# MF_badge_2021_protoshield_ver_B.net
KiCad netlist of a schematic drawn in EAGLE
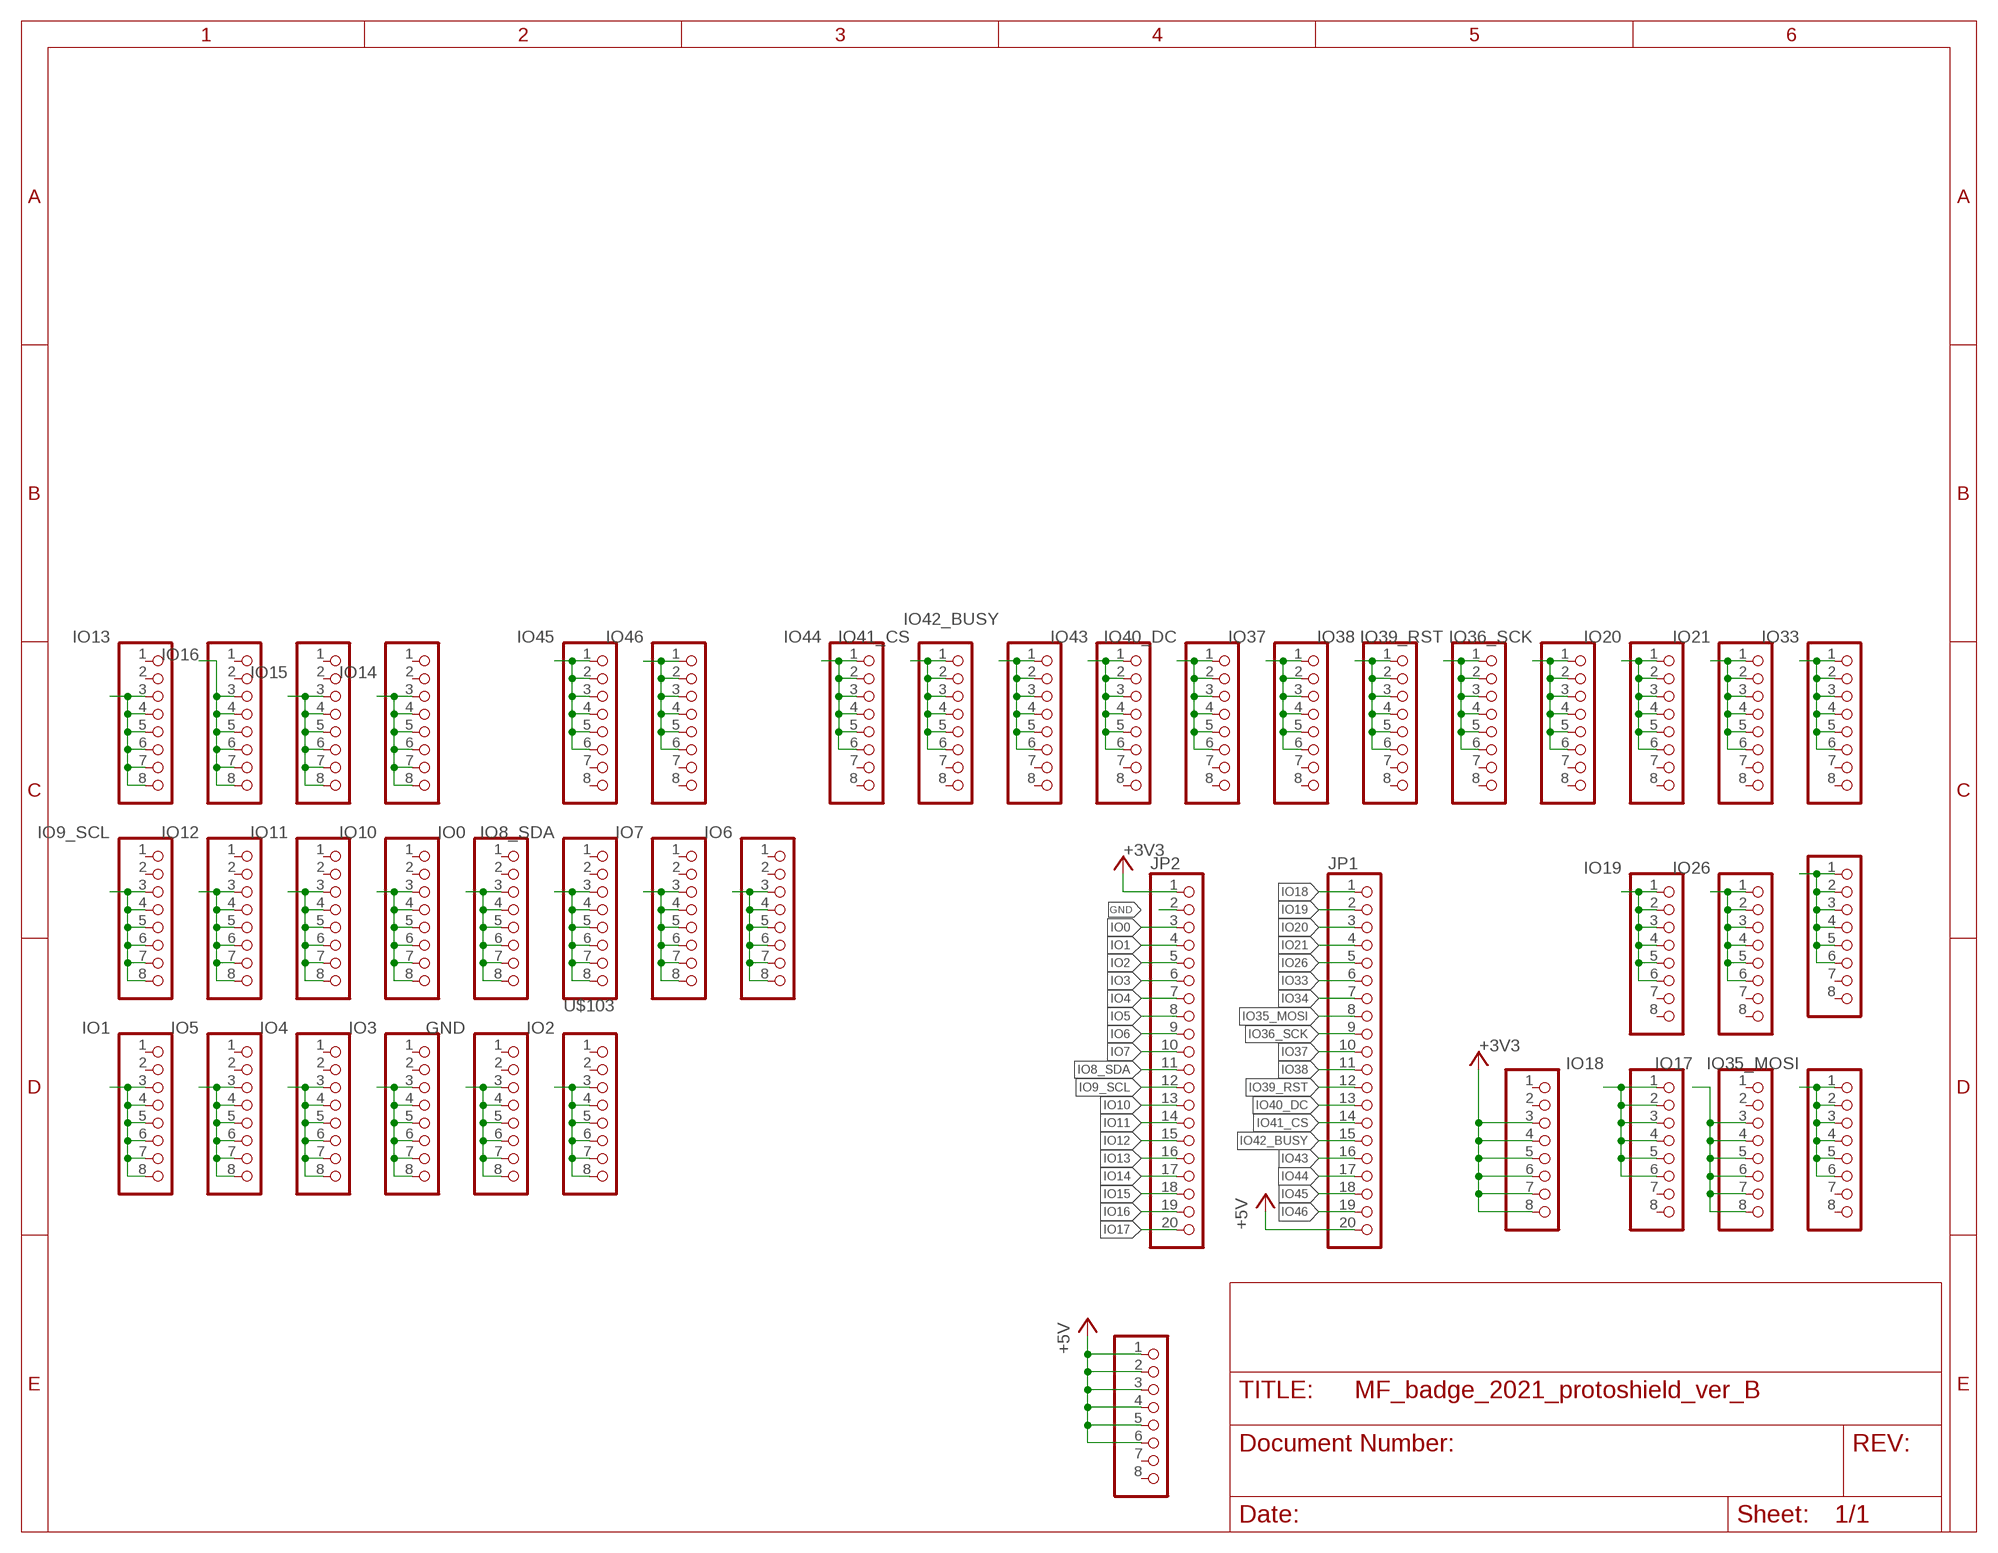
[diagram p0: schematic, sheet 1]

(export (version "E")
  (design (tool "Eeschema 10.0.6"))
  (components
    (comp (ref "JP1")
      (value "PINHD-1X20_CLEANBIG")
      (footprint "eagle-import:1X20-CLEANBIG")
      (libsource (lib "eagle-import") (part "PINHD-1X20_CLEANBIG"))
    )
    (comp (ref "JP2")
      (value "PINHD-1X20_CLEANBIG")
      (footprint "eagle-import:1X20-CLEANBIG")
      (libsource (lib "eagle-import") (part "PINHD-1X20_CLEANBIG"))
    )
    (comp (ref "U$1")
      (value "PINHD-1X8CLEANBIG")
      (footprint "eagle-import:1X08-CLEANBIG")
      (libsource (lib "eagle-import") (part "PINHD-1X8CLEANBIG"))
    )
    (comp (ref "U$5")
      (value "PINHD-1X8CLEANBIG")
      (footprint "eagle-import:1X08-CLEANBIG")
      (libsource (lib "eagle-import") (part "PINHD-1X8CLEANBIG"))
    )
    (comp (ref "U$7")
      (value "PINHD-1X8CLEANBIG")
      (footprint "eagle-import:1X08-CLEANBIG")
      (libsource (lib "eagle-import") (part "PINHD-1X8CLEANBIG"))
    )
    (comp (ref "U$8")
      (value "PINHD-1X8CLEANBIG")
      (footprint "eagle-import:1X08-CLEANBIG")
      (libsource (lib "eagle-import") (part "PINHD-1X8CLEANBIG"))
    )
    (comp (ref "U$9")
      (value "PINHD-1X8CLEANBIG")
      (footprint "eagle-import:1X08-CLEANBIG")
      (libsource (lib "eagle-import") (part "PINHD-1X8CLEANBIG"))
    )
    (comp (ref "U$10")
      (value "PINHD-1X8CLEANBIG")
      (footprint "eagle-import:1X08-CLEANBIG")
      (libsource (lib "eagle-import") (part "PINHD-1X8CLEANBIG"))
    )
    (comp (ref "U$11")
      (value "PINHD-1X8CLEANBIG")
      (footprint "eagle-import:1X08-CLEANBIG")
      (libsource (lib "eagle-import") (part "PINHD-1X8CLEANBIG"))
    )
    (comp (ref "U$12")
      (value "PINHD-1X8CLEANBIG")
      (footprint "eagle-import:1X08-CLEANBIG")
      (libsource (lib "eagle-import") (part "PINHD-1X8CLEANBIG"))
    )
    (comp (ref "U$13")
      (value "PINHD-1X8CLEANBIG")
      (footprint "eagle-import:1X08-CLEANBIG")
      (libsource (lib "eagle-import") (part "PINHD-1X8CLEANBIG"))
    )
    (comp (ref "U$14")
      (value "PINHD-1X8CLEANBIG")
      (footprint "eagle-import:1X08-CLEANBIG")
      (libsource (lib "eagle-import") (part "PINHD-1X8CLEANBIG"))
    )
    (comp (ref "U$15")
      (value "PINHD-1X8CLEANBIG")
      (footprint "eagle-import:1X08-CLEANBIG")
      (libsource (lib "eagle-import") (part "PINHD-1X8CLEANBIG"))
    )
    (comp (ref "U$36")
      (value "PINHD-1X8CLEANBIG")
      (footprint "eagle-import:1X08-CLEANBIG")
      (libsource (lib "eagle-import") (part "PINHD-1X8CLEANBIG"))
    )
    (comp (ref "U$52")
      (value "PINHD-1X8CLEANBIG")
      (footprint "eagle-import:1X08-CLEANBIG")
      (libsource (lib "eagle-import") (part "PINHD-1X8CLEANBIG"))
    )
    (comp (ref "U$53")
      (value "PINHD-1X8CLEANBIG")
      (footprint "eagle-import:1X08-CLEANBIG")
      (libsource (lib "eagle-import") (part "PINHD-1X8CLEANBIG"))
    )
    (comp (ref "U$54")
      (value "PINHD-1X8CLEANBIG")
      (footprint "eagle-import:1X08-CLEANBIG")
      (libsource (lib "eagle-import") (part "PINHD-1X8CLEANBIG"))
    )
    (comp (ref "U$55")
      (value "PINHD-1X8CLEANBIG")
      (footprint "eagle-import:1X08-CLEANBIG")
      (libsource (lib "eagle-import") (part "PINHD-1X8CLEANBIG"))
    )
    (comp (ref "U$56")
      (value "PINHD-1X8CLEANBIG")
      (footprint "eagle-import:1X08-CLEANBIG")
      (libsource (lib "eagle-import") (part "PINHD-1X8CLEANBIG"))
    )
    (comp (ref "U$61")
      (value "PINHD-1X8CLEANBIG")
      (footprint "eagle-import:1X08-CLEANBIG")
      (libsource (lib "eagle-import") (part "PINHD-1X8CLEANBIG"))
    )
    (comp (ref "U$62")
      (value "PINHD-1X8CLEANBIG")
      (footprint "eagle-import:1X08-CLEANBIG")
      (libsource (lib "eagle-import") (part "PINHD-1X8CLEANBIG"))
    )
    (comp (ref "U$63")
      (value "PINHD-1X8CLEANBIG")
      (footprint "eagle-import:1X08-CLEANBIG")
      (libsource (lib "eagle-import") (part "PINHD-1X8CLEANBIG"))
    )
    (comp (ref "U$64")
      (value "PINHD-1X8CLEANBIG")
      (footprint "eagle-import:1X08-CLEANBIG")
      (libsource (lib "eagle-import") (part "PINHD-1X8CLEANBIG"))
    )
    (comp (ref "U$102")
      (value "PINHD-1X8CLEANBIG")
      (footprint "eagle-import:1X08-CLEANBIG")
      (libsource (lib "eagle-import") (part "PINHD-1X8CLEANBIG"))
    )
    (comp (ref "U$103")
      (value "PINHD-1X8CLEANBIG")
      (footprint "eagle-import:1X08-CLEANBIG")
      (libsource (lib "eagle-import") (part "PINHD-1X8CLEANBIG"))
    )
    (comp (ref "U$104")
      (value "PINHD-1X8CLEANBIG")
      (footprint "eagle-import:1X08-CLEANBIG")
      (libsource (lib "eagle-import") (part "PINHD-1X8CLEANBIG"))
    )
    (comp (ref "U$105")
      (value "PINHD-1X8CLEANBIG")
      (footprint "eagle-import:1X08-CLEANBIG")
      (libsource (lib "eagle-import") (part "PINHD-1X8CLEANBIG"))
    )
    (comp (ref "U$106")
      (value "PINHD-1X8CLEANBIG")
      (footprint "eagle-import:1X08-CLEANBIG")
      (libsource (lib "eagle-import") (part "PINHD-1X8CLEANBIG"))
    )
    (comp (ref "U$107")
      (value "PINHD-1X8CLEANBIG")
      (footprint "eagle-import:1X08-CLEANBIG")
      (libsource (lib "eagle-import") (part "PINHD-1X8CLEANBIG"))
    )
    (comp (ref "U$108")
      (value "PINHD-1X8CLEANBIG")
      (footprint "eagle-import:1X08-CLEANBIG")
      (libsource (lib "eagle-import") (part "PINHD-1X8CLEANBIG"))
    )
    (comp (ref "U$109")
      (value "PINHD-1X8CLEANBIG")
      (footprint "eagle-import:1X08-CLEANBIG")
      (libsource (lib "eagle-import") (part "PINHD-1X8CLEANBIG"))
    )
    (comp (ref "U$110")
      (value "PINHD-1X8CLEANBIG")
      (footprint "eagle-import:1X08-CLEANBIG")
      (libsource (lib "eagle-import") (part "PINHD-1X8CLEANBIG"))
    )
    (comp (ref "U$111")
      (value "PINHD-1X8CLEANBIG")
      (footprint "eagle-import:1X08-CLEANBIG")
      (libsource (lib "eagle-import") (part "PINHD-1X8CLEANBIG"))
    )
    (comp (ref "U$112")
      (value "PINHD-1X8CLEANBIG")
      (footprint "eagle-import:1X08-CLEANBIG")
      (libsource (lib "eagle-import") (part "PINHD-1X8CLEANBIG"))
    )
    (comp (ref "U$113")
      (value "PINHD-1X8CLEANBIG")
      (footprint "eagle-import:1X08-CLEANBIG")
      (libsource (lib "eagle-import") (part "PINHD-1X8CLEANBIG"))
    )
    (comp (ref "U$114")
      (value "PINHD-1X8CLEANBIG")
      (footprint "eagle-import:1X08-CLEANBIG")
      (libsource (lib "eagle-import") (part "PINHD-1X8CLEANBIG"))
    )
    (comp (ref "U$115")
      (value "PINHD-1X8CLEANBIG")
      (footprint "eagle-import:1X08-CLEANBIG")
      (libsource (lib "eagle-import") (part "PINHD-1X8CLEANBIG"))
    )
    (comp (ref "U$116")
      (value "PINHD-1X8CLEANBIG")
      (footprint "eagle-import:1X08-CLEANBIG")
      (libsource (lib "eagle-import") (part "PINHD-1X8CLEANBIG"))
    )
    (comp (ref "U$117")
      (value "PINHD-1X8CLEANBIG")
      (footprint "eagle-import:1X08-CLEANBIG")
      (libsource (lib "eagle-import") (part "PINHD-1X8CLEANBIG"))
    )
    (comp (ref "U$118")
      (value "PINHD-1X8CLEANBIG")
      (footprint "eagle-import:1X08-CLEANBIG")
      (libsource (lib "eagle-import") (part "PINHD-1X8CLEANBIG"))
    )
    (comp (ref "U$119")
      (value "PINHD-1X8CLEANBIG")
      (footprint "eagle-import:1X08-CLEANBIG")
      (libsource (lib "eagle-import") (part "PINHD-1X8CLEANBIG"))
    )
    (comp (ref "U$120")
      (value "PINHD-1X8CLEANBIG")
      (footprint "eagle-import:1X08-CLEANBIG")
      (libsource (lib "eagle-import") (part "PINHD-1X8CLEANBIG"))
    )
  )
  (nets
    (net (code "1") (name "+3V3") (class "Default")
      (node (ref "JP2") (pin "1") (pinfunction "1_1") (pintype "passive"))
      (node (ref "U$1") (pin "3") (pinfunction "3_3") (pintype "passive"))
      (node (ref "U$1") (pin "4") (pinfunction "4_4") (pintype "passive"))
      (node (ref "U$1") (pin "5") (pinfunction "5_5") (pintype "passive"))
      (node (ref "U$1") (pin "6") (pinfunction "6_6") (pintype "passive"))
      (node (ref "U$1") (pin "7") (pinfunction "7_7") (pintype "passive"))
      (node (ref "U$1") (pin "8") (pinfunction "8_8") (pintype "passive"))
    )
    (net (code "2") (name "+5V") (class "Default")
      (node (ref "JP1") (pin "20") (pinfunction "20_20") (pintype "passive"))
      (node (ref "U$102") (pin "1") (pinfunction "1_1") (pintype "passive"))
      (node (ref "U$102") (pin "2") (pinfunction "2_2") (pintype "passive"))
      (node (ref "U$102") (pin "3") (pinfunction "3_3") (pintype "passive"))
      (node (ref "U$102") (pin "4") (pinfunction "4_4") (pintype "passive"))
      (node (ref "U$102") (pin "5") (pinfunction "5_5") (pintype "passive"))
      (node (ref "U$102") (pin "6") (pinfunction "6_6") (pintype "passive"))
    )
    (net (code "3") (name "GND") (class "Default")
      (node (ref "JP2") (pin "2") (pinfunction "2_2") (pintype "passive"))
      (node (ref "U$120") (pin "3") (pinfunction "3_3") (pintype "passive"))
      (node (ref "U$120") (pin "4") (pinfunction "4_4") (pintype "passive"))
      (node (ref "U$120") (pin "5") (pinfunction "5_5") (pintype "passive"))
      (node (ref "U$120") (pin "6") (pinfunction "6_6") (pintype "passive"))
      (node (ref "U$120") (pin "7") (pinfunction "7_7") (pintype "passive"))
      (node (ref "U$120") (pin "8") (pinfunction "8_8") (pintype "passive"))
    )
    (net (code "4") (name "IO0") (class "Default")
      (node (ref "JP2") (pin "3") (pinfunction "3_3") (pintype "passive"))
      (node (ref "U$115") (pin "3") (pinfunction "3_3") (pintype "passive"))
      (node (ref "U$115") (pin "4") (pinfunction "4_4") (pintype "passive"))
      (node (ref "U$115") (pin "5") (pinfunction "5_5") (pintype "passive"))
      (node (ref "U$115") (pin "6") (pinfunction "6_6") (pintype "passive"))
      (node (ref "U$115") (pin "7") (pinfunction "7_7") (pintype "passive"))
      (node (ref "U$115") (pin "8") (pinfunction "8_8") (pintype "passive"))
    )
    (net (code "5") (name "IO1") (class "Default")
      (node (ref "JP2") (pin "4") (pinfunction "4_4") (pintype "passive"))
      (node (ref "U$119") (pin "3") (pinfunction "3_3") (pintype "passive"))
      (node (ref "U$119") (pin "4") (pinfunction "4_4") (pintype "passive"))
      (node (ref "U$119") (pin "5") (pinfunction "5_5") (pintype "passive"))
      (node (ref "U$119") (pin "6") (pinfunction "6_6") (pintype "passive"))
      (node (ref "U$119") (pin "7") (pinfunction "7_7") (pintype "passive"))
      (node (ref "U$119") (pin "8") (pinfunction "8_8") (pintype "passive"))
    )
    (net (code "6") (name "IO2") (class "Default")
      (node (ref "JP2") (pin "5") (pinfunction "5_5") (pintype "passive"))
      (node (ref "U$103") (pin "3") (pinfunction "3_3") (pintype "passive"))
      (node (ref "U$103") (pin "4") (pinfunction "4_4") (pintype "passive"))
      (node (ref "U$103") (pin "5") (pinfunction "5_5") (pintype "passive"))
      (node (ref "U$103") (pin "6") (pinfunction "6_6") (pintype "passive"))
      (node (ref "U$103") (pin "7") (pinfunction "7_7") (pintype "passive"))
      (node (ref "U$103") (pin "8") (pinfunction "8_8") (pintype "passive"))
    )
    (net (code "7") (name "IO3") (class "Default")
      (node (ref "JP2") (pin "6") (pinfunction "6_6") (pintype "passive"))
      (node (ref "U$118") (pin "3") (pinfunction "3_3") (pintype "passive"))
      (node (ref "U$118") (pin "4") (pinfunction "4_4") (pintype "passive"))
      (node (ref "U$118") (pin "5") (pinfunction "5_5") (pintype "passive"))
      (node (ref "U$118") (pin "6") (pinfunction "6_6") (pintype "passive"))
      (node (ref "U$118") (pin "7") (pinfunction "7_7") (pintype "passive"))
      (node (ref "U$118") (pin "8") (pinfunction "8_8") (pintype "passive"))
    )
    (net (code "8") (name "IO4") (class "Default")
      (node (ref "JP2") (pin "7") (pinfunction "7_7") (pintype "passive"))
      (node (ref "U$117") (pin "3") (pinfunction "3_3") (pintype "passive"))
      (node (ref "U$117") (pin "4") (pinfunction "4_4") (pintype "passive"))
      (node (ref "U$117") (pin "5") (pinfunction "5_5") (pintype "passive"))
      (node (ref "U$117") (pin "6") (pinfunction "6_6") (pintype "passive"))
      (node (ref "U$117") (pin "7") (pinfunction "7_7") (pintype "passive"))
      (node (ref "U$117") (pin "8") (pinfunction "8_8") (pintype "passive"))
    )
    (net (code "9") (name "IO5") (class "Default")
      (node (ref "JP2") (pin "8") (pinfunction "8_8") (pintype "passive"))
      (node (ref "U$116") (pin "3") (pinfunction "3_3") (pintype "passive"))
      (node (ref "U$116") (pin "4") (pinfunction "4_4") (pintype "passive"))
      (node (ref "U$116") (pin "5") (pinfunction "5_5") (pintype "passive"))
      (node (ref "U$116") (pin "6") (pinfunction "6_6") (pintype "passive"))
      (node (ref "U$116") (pin "7") (pinfunction "7_7") (pintype "passive"))
      (node (ref "U$116") (pin "8") (pinfunction "8_8") (pintype "passive"))
    )
    (net (code "10") (name "IO6") (class "Default")
      (node (ref "JP2") (pin "9") (pinfunction "9_9") (pintype "passive"))
      (node (ref "U$114") (pin "3") (pinfunction "3_3") (pintype "passive"))
      (node (ref "U$114") (pin "4") (pinfunction "4_4") (pintype "passive"))
      (node (ref "U$114") (pin "5") (pinfunction "5_5") (pintype "passive"))
      (node (ref "U$114") (pin "6") (pinfunction "6_6") (pintype "passive"))
      (node (ref "U$114") (pin "7") (pinfunction "7_7") (pintype "passive"))
      (node (ref "U$114") (pin "8") (pinfunction "8_8") (pintype "passive"))
    )
    (net (code "11") (name "IO7") (class "Default")
      (node (ref "JP2") (pin "10") (pinfunction "10_10") (pintype "passive"))
      (node (ref "U$113") (pin "3") (pinfunction "3_3") (pintype "passive"))
      (node (ref "U$113") (pin "4") (pinfunction "4_4") (pintype "passive"))
      (node (ref "U$113") (pin "5") (pinfunction "5_5") (pintype "passive"))
      (node (ref "U$113") (pin "6") (pinfunction "6_6") (pintype "passive"))
      (node (ref "U$113") (pin "7") (pinfunction "7_7") (pintype "passive"))
      (node (ref "U$113") (pin "8") (pinfunction "8_8") (pintype "passive"))
    )
    (net (code "12") (name "IO8_SDA") (class "Default")
      (node (ref "JP2") (pin "11") (pinfunction "11_11") (pintype "passive"))
      (node (ref "U$112") (pin "3") (pinfunction "3_3") (pintype "passive"))
      (node (ref "U$112") (pin "4") (pinfunction "4_4") (pintype "passive"))
      (node (ref "U$112") (pin "5") (pinfunction "5_5") (pintype "passive"))
      (node (ref "U$112") (pin "6") (pinfunction "6_6") (pintype "passive"))
      (node (ref "U$112") (pin "7") (pinfunction "7_7") (pintype "passive"))
      (node (ref "U$112") (pin "8") (pinfunction "8_8") (pintype "passive"))
    )
    (net (code "13") (name "IO9_SCL") (class "Default")
      (node (ref "JP2") (pin "12") (pinfunction "12_12") (pintype "passive"))
      (node (ref "U$111") (pin "3") (pinfunction "3_3") (pintype "passive"))
      (node (ref "U$111") (pin "4") (pinfunction "4_4") (pintype "passive"))
      (node (ref "U$111") (pin "5") (pinfunction "5_5") (pintype "passive"))
      (node (ref "U$111") (pin "6") (pinfunction "6_6") (pintype "passive"))
      (node (ref "U$111") (pin "7") (pinfunction "7_7") (pintype "passive"))
      (node (ref "U$111") (pin "8") (pinfunction "8_8") (pintype "passive"))
    )
    (net (code "14") (name "IO10") (class "Default")
      (node (ref "JP2") (pin "13") (pinfunction "13_13") (pintype "passive"))
      (node (ref "U$110") (pin "3") (pinfunction "3_3") (pintype "passive"))
      (node (ref "U$110") (pin "4") (pinfunction "4_4") (pintype "passive"))
      (node (ref "U$110") (pin "5") (pinfunction "5_5") (pintype "passive"))
      (node (ref "U$110") (pin "6") (pinfunction "6_6") (pintype "passive"))
      (node (ref "U$110") (pin "7") (pinfunction "7_7") (pintype "passive"))
      (node (ref "U$110") (pin "8") (pinfunction "8_8") (pintype "passive"))
    )
    (net (code "15") (name "IO11") (class "Default")
      (node (ref "JP2") (pin "14") (pinfunction "14_14") (pintype "passive"))
      (node (ref "U$109") (pin "3") (pinfunction "3_3") (pintype "passive"))
      (node (ref "U$109") (pin "4") (pinfunction "4_4") (pintype "passive"))
      (node (ref "U$109") (pin "5") (pinfunction "5_5") (pintype "passive"))
      (node (ref "U$109") (pin "6") (pinfunction "6_6") (pintype "passive"))
      (node (ref "U$109") (pin "7") (pinfunction "7_7") (pintype "passive"))
      (node (ref "U$109") (pin "8") (pinfunction "8_8") (pintype "passive"))
    )
    (net (code "16") (name "IO12") (class "Default")
      (node (ref "JP2") (pin "15") (pinfunction "15_15") (pintype "passive"))
      (node (ref "U$108") (pin "3") (pinfunction "3_3") (pintype "passive"))
      (node (ref "U$108") (pin "4") (pinfunction "4_4") (pintype "passive"))
      (node (ref "U$108") (pin "5") (pinfunction "5_5") (pintype "passive"))
      (node (ref "U$108") (pin "6") (pinfunction "6_6") (pintype "passive"))
      (node (ref "U$108") (pin "7") (pinfunction "7_7") (pintype "passive"))
      (node (ref "U$108") (pin "8") (pinfunction "8_8") (pintype "passive"))
    )
    (net (code "17") (name "IO13") (class "Default")
      (node (ref "JP2") (pin "16") (pinfunction "16_16") (pintype "passive"))
      (node (ref "U$107") (pin "3") (pinfunction "3_3") (pintype "passive"))
      (node (ref "U$107") (pin "4") (pinfunction "4_4") (pintype "passive"))
      (node (ref "U$107") (pin "5") (pinfunction "5_5") (pintype "passive"))
      (node (ref "U$107") (pin "6") (pinfunction "6_6") (pintype "passive"))
      (node (ref "U$107") (pin "7") (pinfunction "7_7") (pintype "passive"))
      (node (ref "U$107") (pin "8") (pinfunction "8_8") (pintype "passive"))
    )
    (net (code "18") (name "IO14") (class "Default")
      (node (ref "JP2") (pin "17") (pinfunction "17_17") (pintype "passive"))
      (node (ref "U$106") (pin "3") (pinfunction "3_3") (pintype "passive"))
      (node (ref "U$106") (pin "4") (pinfunction "4_4") (pintype "passive"))
      (node (ref "U$106") (pin "5") (pinfunction "5_5") (pintype "passive"))
      (node (ref "U$106") (pin "6") (pinfunction "6_6") (pintype "passive"))
      (node (ref "U$106") (pin "7") (pinfunction "7_7") (pintype "passive"))
      (node (ref "U$106") (pin "8") (pinfunction "8_8") (pintype "passive"))
    )
    (net (code "19") (name "IO15") (class "Default")
      (node (ref "JP2") (pin "18") (pinfunction "18_18") (pintype "passive"))
      (node (ref "U$105") (pin "3") (pinfunction "3_3") (pintype "passive"))
      (node (ref "U$105") (pin "4") (pinfunction "4_4") (pintype "passive"))
      (node (ref "U$105") (pin "5") (pinfunction "5_5") (pintype "passive"))
      (node (ref "U$105") (pin "6") (pinfunction "6_6") (pintype "passive"))
      (node (ref "U$105") (pin "7") (pinfunction "7_7") (pintype "passive"))
      (node (ref "U$105") (pin "8") (pinfunction "8_8") (pintype "passive"))
    )
    (net (code "20") (name "IO16") (class "Default")
      (node (ref "JP2") (pin "19") (pinfunction "19_19") (pintype "passive"))
      (node (ref "U$104") (pin "3") (pinfunction "3_3") (pintype "passive"))
      (node (ref "U$104") (pin "4") (pinfunction "4_4") (pintype "passive"))
      (node (ref "U$104") (pin "5") (pinfunction "5_5") (pintype "passive"))
      (node (ref "U$104") (pin "6") (pinfunction "6_6") (pintype "passive"))
      (node (ref "U$104") (pin "7") (pinfunction "7_7") (pintype "passive"))
      (node (ref "U$104") (pin "8") (pinfunction "8_8") (pintype "passive"))
    )
    (net (code "21") (name "IO17") (class "Default")
      (node (ref "JP2") (pin "20") (pinfunction "20_20") (pintype "passive"))
      (node (ref "U$7") (pin "3") (pinfunction "3_3") (pintype "passive"))
      (node (ref "U$7") (pin "4") (pinfunction "4_4") (pintype "passive"))
      (node (ref "U$7") (pin "5") (pinfunction "5_5") (pintype "passive"))
      (node (ref "U$7") (pin "6") (pinfunction "6_6") (pintype "passive"))
      (node (ref "U$7") (pin "7") (pinfunction "7_7") (pintype "passive"))
      (node (ref "U$7") (pin "8") (pinfunction "8_8") (pintype "passive"))
    )
    (net (code "22") (name "IO18") (class "Default")
      (node (ref "JP1") (pin "1") (pinfunction "1_1") (pintype "passive"))
      (node (ref "U$5") (pin "1") (pinfunction "1_1") (pintype "passive"))
      (node (ref "U$5") (pin "2") (pinfunction "2_2") (pintype "passive"))
      (node (ref "U$5") (pin "3") (pinfunction "3_3") (pintype "passive"))
      (node (ref "U$5") (pin "4") (pinfunction "4_4") (pintype "passive"))
      (node (ref "U$5") (pin "5") (pinfunction "5_5") (pintype "passive"))
      (node (ref "U$5") (pin "6") (pinfunction "6_6") (pintype "passive"))
    )
    (net (code "23") (name "IO19") (class "Default")
      (node (ref "JP1") (pin "2") (pinfunction "2_2") (pintype "passive"))
      (node (ref "U$8") (pin "1") (pinfunction "1_1") (pintype "passive"))
      (node (ref "U$8") (pin "2") (pinfunction "2_2") (pintype "passive"))
      (node (ref "U$8") (pin "3") (pinfunction "3_3") (pintype "passive"))
      (node (ref "U$8") (pin "4") (pinfunction "4_4") (pintype "passive"))
      (node (ref "U$8") (pin "5") (pinfunction "5_5") (pintype "passive"))
      (node (ref "U$8") (pin "6") (pinfunction "6_6") (pintype "passive"))
    )
    (net (code "24") (name "IO20") (class "Default")
      (node (ref "JP1") (pin "3") (pinfunction "3_3") (pintype "passive"))
      (node (ref "U$9") (pin "1") (pinfunction "1_1") (pintype "passive"))
      (node (ref "U$9") (pin "2") (pinfunction "2_2") (pintype "passive"))
      (node (ref "U$9") (pin "3") (pinfunction "3_3") (pintype "passive"))
      (node (ref "U$9") (pin "4") (pinfunction "4_4") (pintype "passive"))
      (node (ref "U$9") (pin "5") (pinfunction "5_5") (pintype "passive"))
      (node (ref "U$9") (pin "6") (pinfunction "6_6") (pintype "passive"))
    )
    (net (code "25") (name "IO21") (class "Default")
      (node (ref "JP1") (pin "4") (pinfunction "4_4") (pintype "passive"))
      (node (ref "U$10") (pin "1") (pinfunction "1_1") (pintype "passive"))
      (node (ref "U$10") (pin "2") (pinfunction "2_2") (pintype "passive"))
      (node (ref "U$10") (pin "3") (pinfunction "3_3") (pintype "passive"))
      (node (ref "U$10") (pin "4") (pinfunction "4_4") (pintype "passive"))
      (node (ref "U$10") (pin "5") (pinfunction "5_5") (pintype "passive"))
      (node (ref "U$10") (pin "6") (pinfunction "6_6") (pintype "passive"))
    )
    (net (code "26") (name "IO26") (class "Default")
      (node (ref "JP1") (pin "5") (pinfunction "5_5") (pintype "passive"))
      (node (ref "U$11") (pin "1") (pinfunction "1_1") (pintype "passive"))
      (node (ref "U$11") (pin "2") (pinfunction "2_2") (pintype "passive"))
      (node (ref "U$11") (pin "3") (pinfunction "3_3") (pintype "passive"))
      (node (ref "U$11") (pin "4") (pinfunction "4_4") (pintype "passive"))
      (node (ref "U$11") (pin "5") (pinfunction "5_5") (pintype "passive"))
      (node (ref "U$11") (pin "6") (pinfunction "6_6") (pintype "passive"))
    )
    (net (code "27") (name "IO33") (class "Default")
      (node (ref "JP1") (pin "6") (pinfunction "6_6") (pintype "passive"))
      (node (ref "U$12") (pin "1") (pinfunction "1_1") (pintype "passive"))
      (node (ref "U$12") (pin "2") (pinfunction "2_2") (pintype "passive"))
      (node (ref "U$12") (pin "3") (pinfunction "3_3") (pintype "passive"))
      (node (ref "U$12") (pin "4") (pinfunction "4_4") (pintype "passive"))
      (node (ref "U$12") (pin "5") (pinfunction "5_5") (pintype "passive"))
      (node (ref "U$12") (pin "6") (pinfunction "6_6") (pintype "passive"))
    )
    (net (code "28") (name "IO34") (class "Default")
      (node (ref "JP1") (pin "7") (pinfunction "7_7") (pintype "passive"))
      (node (ref "U$13") (pin "1") (pinfunction "1_1") (pintype "passive"))
      (node (ref "U$13") (pin "2") (pinfunction "2_2") (pintype "passive"))
      (node (ref "U$13") (pin "3") (pinfunction "3_3") (pintype "passive"))
      (node (ref "U$13") (pin "4") (pinfunction "4_4") (pintype "passive"))
      (node (ref "U$13") (pin "5") (pinfunction "5_5") (pintype "passive"))
      (node (ref "U$13") (pin "6") (pinfunction "6_6") (pintype "passive"))
    )
    (net (code "29") (name "IO35_MOSI") (class "Default")
      (node (ref "JP1") (pin "8") (pinfunction "8_8") (pintype "passive"))
      (node (ref "U$14") (pin "1") (pinfunction "1_1") (pintype "passive"))
      (node (ref "U$14") (pin "2") (pinfunction "2_2") (pintype "passive"))
      (node (ref "U$14") (pin "3") (pinfunction "3_3") (pintype "passive"))
      (node (ref "U$14") (pin "4") (pinfunction "4_4") (pintype "passive"))
      (node (ref "U$14") (pin "5") (pinfunction "5_5") (pintype "passive"))
      (node (ref "U$14") (pin "6") (pinfunction "6_6") (pintype "passive"))
    )
    (net (code "30") (name "IO36_SCK") (class "Default")
      (node (ref "JP1") (pin "9") (pinfunction "9_9") (pintype "passive"))
      (node (ref "U$15") (pin "1") (pinfunction "1_1") (pintype "passive"))
      (node (ref "U$15") (pin "2") (pinfunction "2_2") (pintype "passive"))
      (node (ref "U$15") (pin "3") (pinfunction "3_3") (pintype "passive"))
      (node (ref "U$15") (pin "4") (pinfunction "4_4") (pintype "passive"))
      (node (ref "U$15") (pin "5") (pinfunction "5_5") (pintype "passive"))
      (node (ref "U$15") (pin "6") (pinfunction "6_6") (pintype "passive"))
    )
    (net (code "31") (name "IO37") (class "Default")
      (node (ref "JP1") (pin "10") (pinfunction "10_10") (pintype "passive"))
      (node (ref "U$36") (pin "1") (pinfunction "1_1") (pintype "passive"))
      (node (ref "U$36") (pin "2") (pinfunction "2_2") (pintype "passive"))
      (node (ref "U$36") (pin "3") (pinfunction "3_3") (pintype "passive"))
      (node (ref "U$36") (pin "4") (pinfunction "4_4") (pintype "passive"))
      (node (ref "U$36") (pin "5") (pinfunction "5_5") (pintype "passive"))
      (node (ref "U$36") (pin "6") (pinfunction "6_6") (pintype "passive"))
    )
    (net (code "32") (name "IO38") (class "Default")
      (node (ref "JP1") (pin "11") (pinfunction "11_11") (pintype "passive"))
      (node (ref "U$52") (pin "1") (pinfunction "1_1") (pintype "passive"))
      (node (ref "U$52") (pin "2") (pinfunction "2_2") (pintype "passive"))
      (node (ref "U$52") (pin "3") (pinfunction "3_3") (pintype "passive"))
      (node (ref "U$52") (pin "4") (pinfunction "4_4") (pintype "passive"))
      (node (ref "U$52") (pin "5") (pinfunction "5_5") (pintype "passive"))
      (node (ref "U$52") (pin "6") (pinfunction "6_6") (pintype "passive"))
    )
    (net (code "33") (name "IO39_RST") (class "Default")
      (node (ref "JP1") (pin "12") (pinfunction "12_12") (pintype "passive"))
      (node (ref "U$53") (pin "1") (pinfunction "1_1") (pintype "passive"))
      (node (ref "U$53") (pin "2") (pinfunction "2_2") (pintype "passive"))
      (node (ref "U$53") (pin "3") (pinfunction "3_3") (pintype "passive"))
      (node (ref "U$53") (pin "4") (pinfunction "4_4") (pintype "passive"))
      (node (ref "U$53") (pin "5") (pinfunction "5_5") (pintype "passive"))
      (node (ref "U$53") (pin "6") (pinfunction "6_6") (pintype "passive"))
    )
    (net (code "34") (name "IO40_DC") (class "Default")
      (node (ref "JP1") (pin "13") (pinfunction "13_13") (pintype "passive"))
      (node (ref "U$54") (pin "1") (pinfunction "1_1") (pintype "passive"))
      (node (ref "U$54") (pin "2") (pinfunction "2_2") (pintype "passive"))
      (node (ref "U$54") (pin "3") (pinfunction "3_3") (pintype "passive"))
      (node (ref "U$54") (pin "4") (pinfunction "4_4") (pintype "passive"))
      (node (ref "U$54") (pin "5") (pinfunction "5_5") (pintype "passive"))
      (node (ref "U$54") (pin "6") (pinfunction "6_6") (pintype "passive"))
    )
    (net (code "35") (name "IO41_CS") (class "Default")
      (node (ref "JP1") (pin "14") (pinfunction "14_14") (pintype "passive"))
      (node (ref "U$55") (pin "1") (pinfunction "1_1") (pintype "passive"))
      (node (ref "U$55") (pin "2") (pinfunction "2_2") (pintype "passive"))
      (node (ref "U$55") (pin "3") (pinfunction "3_3") (pintype "passive"))
      (node (ref "U$55") (pin "4") (pinfunction "4_4") (pintype "passive"))
      (node (ref "U$55") (pin "5") (pinfunction "5_5") (pintype "passive"))
      (node (ref "U$55") (pin "6") (pinfunction "6_6") (pintype "passive"))
    )
    (net (code "36") (name "IO42_BUSY") (class "Default")
      (node (ref "JP1") (pin "15") (pinfunction "15_15") (pintype "passive"))
      (node (ref "U$56") (pin "1") (pinfunction "1_1") (pintype "passive"))
      (node (ref "U$56") (pin "2") (pinfunction "2_2") (pintype "passive"))
      (node (ref "U$56") (pin "3") (pinfunction "3_3") (pintype "passive"))
      (node (ref "U$56") (pin "4") (pinfunction "4_4") (pintype "passive"))
      (node (ref "U$56") (pin "5") (pinfunction "5_5") (pintype "passive"))
      (node (ref "U$56") (pin "6") (pinfunction "6_6") (pintype "passive"))
    )
    (net (code "37") (name "IO43") (class "Default")
      (node (ref "JP1") (pin "16") (pinfunction "16_16") (pintype "passive"))
      (node (ref "U$61") (pin "1") (pinfunction "1_1") (pintype "passive"))
      (node (ref "U$61") (pin "2") (pinfunction "2_2") (pintype "passive"))
      (node (ref "U$61") (pin "3") (pinfunction "3_3") (pintype "passive"))
      (node (ref "U$61") (pin "4") (pinfunction "4_4") (pintype "passive"))
      (node (ref "U$61") (pin "5") (pinfunction "5_5") (pintype "passive"))
      (node (ref "U$61") (pin "6") (pinfunction "6_6") (pintype "passive"))
    )
    (net (code "38") (name "IO44") (class "Default")
      (node (ref "JP1") (pin "17") (pinfunction "17_17") (pintype "passive"))
      (node (ref "U$62") (pin "1") (pinfunction "1_1") (pintype "passive"))
      (node (ref "U$62") (pin "2") (pinfunction "2_2") (pintype "passive"))
      (node (ref "U$62") (pin "3") (pinfunction "3_3") (pintype "passive"))
      (node (ref "U$62") (pin "4") (pinfunction "4_4") (pintype "passive"))
      (node (ref "U$62") (pin "5") (pinfunction "5_5") (pintype "passive"))
      (node (ref "U$62") (pin "6") (pinfunction "6_6") (pintype "passive"))
    )
    (net (code "39") (name "IO45") (class "Default")
      (node (ref "JP1") (pin "18") (pinfunction "18_18") (pintype "passive"))
      (node (ref "U$63") (pin "1") (pinfunction "1_1") (pintype "passive"))
      (node (ref "U$63") (pin "2") (pinfunction "2_2") (pintype "passive"))
      (node (ref "U$63") (pin "3") (pinfunction "3_3") (pintype "passive"))
      (node (ref "U$63") (pin "4") (pinfunction "4_4") (pintype "passive"))
      (node (ref "U$63") (pin "5") (pinfunction "5_5") (pintype "passive"))
      (node (ref "U$63") (pin "6") (pinfunction "6_6") (pintype "passive"))
    )
    (net (code "40") (name "IO46") (class "Default")
      (node (ref "JP1") (pin "19") (pinfunction "19_19") (pintype "passive"))
      (node (ref "U$64") (pin "1") (pinfunction "1_1") (pintype "passive"))
      (node (ref "U$64") (pin "2") (pinfunction "2_2") (pintype "passive"))
      (node (ref "U$64") (pin "3") (pinfunction "3_3") (pintype "passive"))
      (node (ref "U$64") (pin "4") (pinfunction "4_4") (pintype "passive"))
      (node (ref "U$64") (pin "5") (pinfunction "5_5") (pintype "passive"))
      (node (ref "U$64") (pin "6") (pinfunction "6_6") (pintype "passive"))
    )
    (net (code "41") (name "unconnected-(U$1-Pad1)") (class "Default")
      (node (ref "U$1") (pin "1") (pinfunction "1_1") (pintype "passive"))
    )
    (net (code "42") (name "unconnected-(U$1-Pad2)") (class "Default")
      (node (ref "U$1") (pin "2") (pinfunction "2_2") (pintype "passive"))
    )
    (net (code "43") (name "unconnected-(U$5-Pad7)") (class "Default")
      (node (ref "U$5") (pin "7") (pinfunction "7_7") (pintype "passive"))
    )
    (net (code "44") (name "unconnected-(U$5-Pad8)") (class "Default")
      (node (ref "U$5") (pin "8") (pinfunction "8_8") (pintype "passive"))
    )
    (net (code "45") (name "unconnected-(U$7-Pad1)") (class "Default")
      (node (ref "U$7") (pin "1") (pinfunction "1_1") (pintype "passive"))
    )
    (net (code "46") (name "unconnected-(U$7-Pad2)") (class "Default")
      (node (ref "U$7") (pin "2") (pinfunction "2_2") (pintype "passive"))
    )
    (net (code "47") (name "unconnected-(U$8-Pad7)") (class "Default")
      (node (ref "U$8") (pin "7") (pinfunction "7_7") (pintype "passive"))
    )
    (net (code "48") (name "unconnected-(U$8-Pad8)") (class "Default")
      (node (ref "U$8") (pin "8") (pinfunction "8_8") (pintype "passive"))
    )
    (net (code "49") (name "unconnected-(U$9-Pad7)") (class "Default")
      (node (ref "U$9") (pin "7") (pinfunction "7_7") (pintype "passive"))
    )
    (net (code "50") (name "unconnected-(U$9-Pad8)") (class "Default")
      (node (ref "U$9") (pin "8") (pinfunction "8_8") (pintype "passive"))
    )
    (net (code "51") (name "unconnected-(U$10-Pad7)") (class "Default")
      (node (ref "U$10") (pin "7") (pinfunction "7_7") (pintype "passive"))
    )
    (net (code "52") (name "unconnected-(U$10-Pad8)") (class "Default")
      (node (ref "U$10") (pin "8") (pinfunction "8_8") (pintype "passive"))
    )
    (net (code "53") (name "unconnected-(U$11-Pad7)") (class "Default")
      (node (ref "U$11") (pin "7") (pinfunction "7_7") (pintype "passive"))
    )
    (net (code "54") (name "unconnected-(U$11-Pad8)") (class "Default")
      (node (ref "U$11") (pin "8") (pinfunction "8_8") (pintype "passive"))
    )
    (net (code "55") (name "unconnected-(U$12-Pad7)") (class "Default")
      (node (ref "U$12") (pin "7") (pinfunction "7_7") (pintype "passive"))
    )
    (net (code "56") (name "unconnected-(U$12-Pad8)") (class "Default")
      (node (ref "U$12") (pin "8") (pinfunction "8_8") (pintype "passive"))
    )
    (net (code "57") (name "unconnected-(U$13-Pad7)") (class "Default")
      (node (ref "U$13") (pin "7") (pinfunction "7_7") (pintype "passive"))
    )
    (net (code "58") (name "unconnected-(U$13-Pad8)") (class "Default")
      (node (ref "U$13") (pin "8") (pinfunction "8_8") (pintype "passive"))
    )
    (net (code "59") (name "unconnected-(U$14-Pad7)") (class "Default")
      (node (ref "U$14") (pin "7") (pinfunction "7_7") (pintype "passive"))
    )
    (net (code "60") (name "unconnected-(U$14-Pad8)") (class "Default")
      (node (ref "U$14") (pin "8") (pinfunction "8_8") (pintype "passive"))
    )
    (net (code "61") (name "unconnected-(U$15-Pad7)") (class "Default")
      (node (ref "U$15") (pin "7") (pinfunction "7_7") (pintype "passive"))
    )
    (net (code "62") (name "unconnected-(U$15-Pad8)") (class "Default")
      (node (ref "U$15") (pin "8") (pinfunction "8_8") (pintype "passive"))
    )
    (net (code "63") (name "unconnected-(U$36-Pad7)") (class "Default")
      (node (ref "U$36") (pin "7") (pinfunction "7_7") (pintype "passive"))
    )
    (net (code "64") (name "unconnected-(U$36-Pad8)") (class "Default")
      (node (ref "U$36") (pin "8") (pinfunction "8_8") (pintype "passive"))
    )
    (net (code "65") (name "unconnected-(U$52-Pad7)") (class "Default")
      (node (ref "U$52") (pin "7") (pinfunction "7_7") (pintype "passive"))
    )
    (net (code "66") (name "unconnected-(U$52-Pad8)") (class "Default")
      (node (ref "U$52") (pin "8") (pinfunction "8_8") (pintype "passive"))
    )
    (net (code "67") (name "unconnected-(U$53-Pad7)") (class "Default")
      (node (ref "U$53") (pin "7") (pinfunction "7_7") (pintype "passive"))
    )
    (net (code "68") (name "unconnected-(U$53-Pad8)") (class "Default")
      (node (ref "U$53") (pin "8") (pinfunction "8_8") (pintype "passive"))
    )
    (net (code "69") (name "unconnected-(U$54-Pad7)") (class "Default")
      (node (ref "U$54") (pin "7") (pinfunction "7_7") (pintype "passive"))
    )
    (net (code "70") (name "unconnected-(U$54-Pad8)") (class "Default")
      (node (ref "U$54") (pin "8") (pinfunction "8_8") (pintype "passive"))
    )
    (net (code "71") (name "unconnected-(U$55-Pad7)") (class "Default")
      (node (ref "U$55") (pin "7") (pinfunction "7_7") (pintype "passive"))
    )
    (net (code "72") (name "unconnected-(U$55-Pad8)") (class "Default")
      (node (ref "U$55") (pin "8") (pinfunction "8_8") (pintype "passive"))
    )
    (net (code "73") (name "unconnected-(U$56-Pad7)") (class "Default")
      (node (ref "U$56") (pin "7") (pinfunction "7_7") (pintype "passive"))
    )
    (net (code "74") (name "unconnected-(U$56-Pad8)") (class "Default")
      (node (ref "U$56") (pin "8") (pinfunction "8_8") (pintype "passive"))
    )
    (net (code "75") (name "unconnected-(U$61-Pad7)") (class "Default")
      (node (ref "U$61") (pin "7") (pinfunction "7_7") (pintype "passive"))
    )
    (net (code "76") (name "unconnected-(U$61-Pad8)") (class "Default")
      (node (ref "U$61") (pin "8") (pinfunction "8_8") (pintype "passive"))
    )
    (net (code "77") (name "unconnected-(U$62-Pad7)") (class "Default")
      (node (ref "U$62") (pin "7") (pinfunction "7_7") (pintype "passive"))
    )
    (net (code "78") (name "unconnected-(U$62-Pad8)") (class "Default")
      (node (ref "U$62") (pin "8") (pinfunction "8_8") (pintype "passive"))
    )
    (net (code "79") (name "unconnected-(U$63-Pad7)") (class "Default")
      (node (ref "U$63") (pin "7") (pinfunction "7_7") (pintype "passive"))
    )
    (net (code "80") (name "unconnected-(U$63-Pad8)") (class "Default")
      (node (ref "U$63") (pin "8") (pinfunction "8_8") (pintype "passive"))
    )
    (net (code "81") (name "unconnected-(U$64-Pad7)") (class "Default")
      (node (ref "U$64") (pin "7") (pinfunction "7_7") (pintype "passive"))
    )
    (net (code "82") (name "unconnected-(U$64-Pad8)") (class "Default")
      (node (ref "U$64") (pin "8") (pinfunction "8_8") (pintype "passive"))
    )
    (net (code "83") (name "unconnected-(U$102-Pad7)") (class "Default")
      (node (ref "U$102") (pin "7") (pinfunction "7_7") (pintype "passive"))
    )
    (net (code "84") (name "unconnected-(U$102-Pad8)") (class "Default")
      (node (ref "U$102") (pin "8") (pinfunction "8_8") (pintype "passive"))
    )
    (net (code "85") (name "unconnected-(U$103-Pad1)") (class "Default")
      (node (ref "U$103") (pin "1") (pinfunction "1_1") (pintype "passive"))
    )
    (net (code "86") (name "unconnected-(U$103-Pad2)") (class "Default")
      (node (ref "U$103") (pin "2") (pinfunction "2_2") (pintype "passive"))
    )
    (net (code "87") (name "unconnected-(U$104-Pad1)") (class "Default")
      (node (ref "U$104") (pin "1") (pinfunction "1_1") (pintype "passive"))
    )
    (net (code "88") (name "unconnected-(U$104-Pad2)") (class "Default")
      (node (ref "U$104") (pin "2") (pinfunction "2_2") (pintype "passive"))
    )
    (net (code "89") (name "unconnected-(U$105-Pad1)") (class "Default")
      (node (ref "U$105") (pin "1") (pinfunction "1_1") (pintype "passive"))
    )
    (net (code "90") (name "unconnected-(U$105-Pad2)") (class "Default")
      (node (ref "U$105") (pin "2") (pinfunction "2_2") (pintype "passive"))
    )
    (net (code "91") (name "unconnected-(U$106-Pad1)") (class "Default")
      (node (ref "U$106") (pin "1") (pinfunction "1_1") (pintype "passive"))
    )
    (net (code "92") (name "unconnected-(U$106-Pad2)") (class "Default")
      (node (ref "U$106") (pin "2") (pinfunction "2_2") (pintype "passive"))
    )
    (net (code "93") (name "unconnected-(U$107-Pad1)") (class "Default")
      (node (ref "U$107") (pin "1") (pinfunction "1_1") (pintype "passive"))
    )
    (net (code "94") (name "unconnected-(U$107-Pad2)") (class "Default")
      (node (ref "U$107") (pin "2") (pinfunction "2_2") (pintype "passive"))
    )
    (net (code "95") (name "unconnected-(U$108-Pad1)") (class "Default")
      (node (ref "U$108") (pin "1") (pinfunction "1_1") (pintype "passive"))
    )
    (net (code "96") (name "unconnected-(U$108-Pad2)") (class "Default")
      (node (ref "U$108") (pin "2") (pinfunction "2_2") (pintype "passive"))
    )
    (net (code "97") (name "unconnected-(U$109-Pad1)") (class "Default")
      (node (ref "U$109") (pin "1") (pinfunction "1_1") (pintype "passive"))
    )
    (net (code "98") (name "unconnected-(U$109-Pad2)") (class "Default")
      (node (ref "U$109") (pin "2") (pinfunction "2_2") (pintype "passive"))
    )
    (net (code "99") (name "unconnected-(U$110-Pad1)") (class "Default")
      (node (ref "U$110") (pin "1") (pinfunction "1_1") (pintype "passive"))
    )
    (net (code "100") (name "unconnected-(U$110-Pad2)") (class "Default")
      (node (ref "U$110") (pin "2") (pinfunction "2_2") (pintype "passive"))
    )
    (net (code "101") (name "unconnected-(U$111-Pad1)") (class "Default")
      (node (ref "U$111") (pin "1") (pinfunction "1_1") (pintype "passive"))
    )
    (net (code "102") (name "unconnected-(U$111-Pad2)") (class "Default")
      (node (ref "U$111") (pin "2") (pinfunction "2_2") (pintype "passive"))
    )
    (net (code "103") (name "unconnected-(U$112-Pad1)") (class "Default")
      (node (ref "U$112") (pin "1") (pinfunction "1_1") (pintype "passive"))
    )
    (net (code "104") (name "unconnected-(U$112-Pad2)") (class "Default")
      (node (ref "U$112") (pin "2") (pinfunction "2_2") (pintype "passive"))
    )
    (net (code "105") (name "unconnected-(U$113-Pad1)") (class "Default")
      (node (ref "U$113") (pin "1") (pinfunction "1_1") (pintype "passive"))
    )
    (net (code "106") (name "unconnected-(U$113-Pad2)") (class "Default")
      (node (ref "U$113") (pin "2") (pinfunction "2_2") (pintype "passive"))
    )
    (net (code "107") (name "unconnected-(U$114-Pad1)") (class "Default")
      (node (ref "U$114") (pin "1") (pinfunction "1_1") (pintype "passive"))
    )
    (net (code "108") (name "unconnected-(U$114-Pad2)") (class "Default")
      (node (ref "U$114") (pin "2") (pinfunction "2_2") (pintype "passive"))
    )
    (net (code "109") (name "unconnected-(U$115-Pad1)") (class "Default")
      (node (ref "U$115") (pin "1") (pinfunction "1_1") (pintype "passive"))
    )
    (net (code "110") (name "unconnected-(U$115-Pad2)") (class "Default")
      (node (ref "U$115") (pin "2") (pinfunction "2_2") (pintype "passive"))
    )
    (net (code "111") (name "unconnected-(U$116-Pad1)") (class "Default")
      (node (ref "U$116") (pin "1") (pinfunction "1_1") (pintype "passive"))
    )
    (net (code "112") (name "unconnected-(U$116-Pad2)") (class "Default")
      (node (ref "U$116") (pin "2") (pinfunction "2_2") (pintype "passive"))
    )
    (net (code "113") (name "unconnected-(U$117-Pad1)") (class "Default")
      (node (ref "U$117") (pin "1") (pinfunction "1_1") (pintype "passive"))
    )
    (net (code "114") (name "unconnected-(U$117-Pad2)") (class "Default")
      (node (ref "U$117") (pin "2") (pinfunction "2_2") (pintype "passive"))
    )
    (net (code "115") (name "unconnected-(U$118-Pad1)") (class "Default")
      (node (ref "U$118") (pin "1") (pinfunction "1_1") (pintype "passive"))
    )
    (net (code "116") (name "unconnected-(U$118-Pad2)") (class "Default")
      (node (ref "U$118") (pin "2") (pinfunction "2_2") (pintype "passive"))
    )
    (net (code "117") (name "unconnected-(U$119-Pad1)") (class "Default")
      (node (ref "U$119") (pin "1") (pinfunction "1_1") (pintype "passive"))
    )
    (net (code "118") (name "unconnected-(U$119-Pad2)") (class "Default")
      (node (ref "U$119") (pin "2") (pinfunction "2_2") (pintype "passive"))
    )
    (net (code "119") (name "unconnected-(U$120-Pad1)") (class "Default")
      (node (ref "U$120") (pin "1") (pinfunction "1_1") (pintype "passive"))
    )
    (net (code "120") (name "unconnected-(U$120-Pad2)") (class "Default")
      (node (ref "U$120") (pin "2") (pinfunction "2_2") (pintype "passive"))
    )
  )
)
